# Floppy_V2_5_1_production.net
KiCad netlist of a schematic drawn in EAGLE
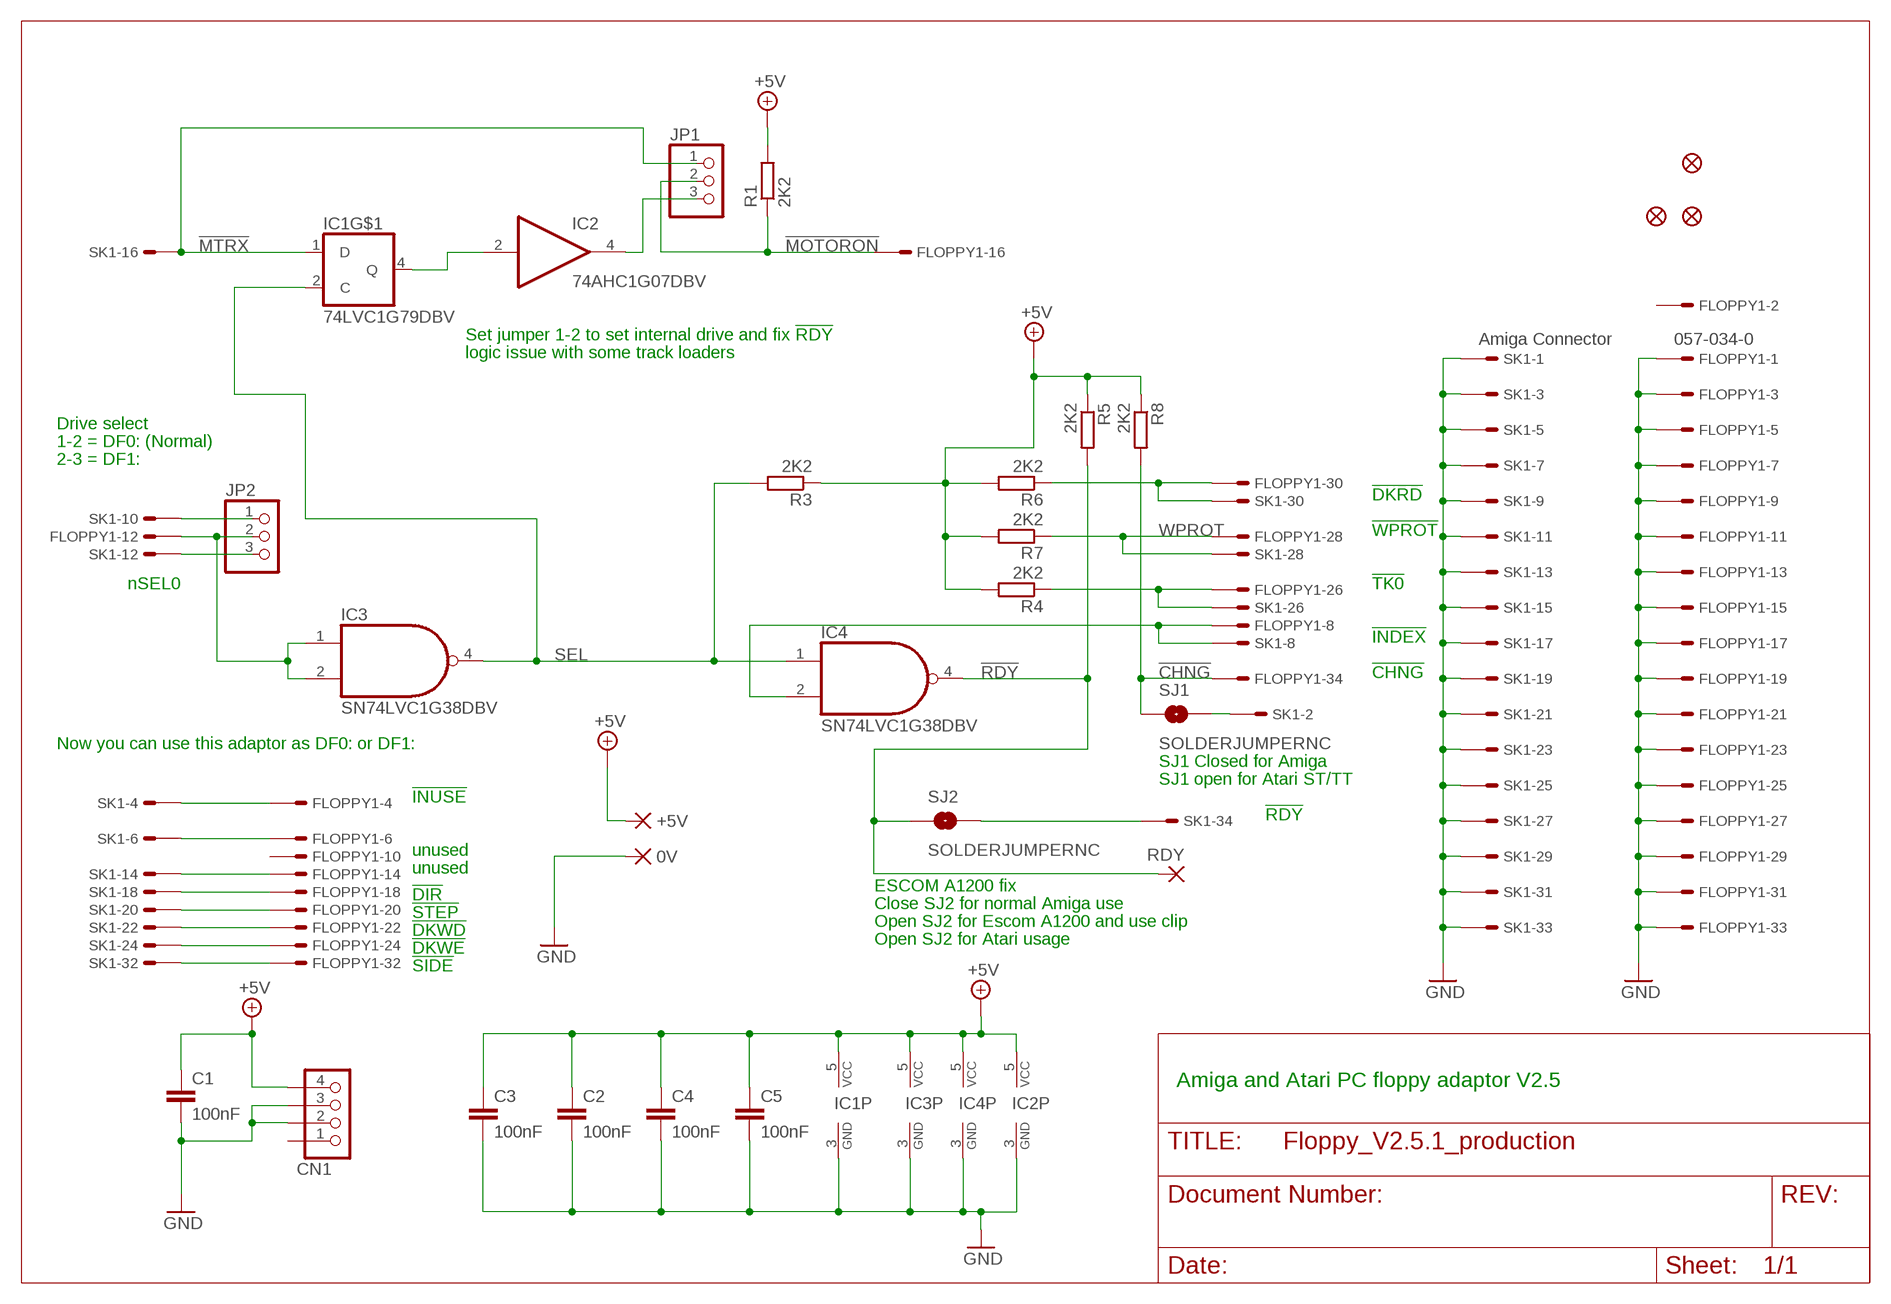
[diagram p0: schematic, sheet 1]

(export (version "E")
  (design (tool "Eeschema 10.0.6"))
  (components
    (comp (ref "+5V")
      (value "PAD-0360-S")
      (footprint "eagle-import:0360-S")
      (libsource (lib "eagle-import") (part "PAD-0360-S"))
    )
    (comp (ref "0V")
      (value "PAD-0360-S")
      (footprint "eagle-import:0360-S")
      (libsource (lib "eagle-import") (part "PAD-0360-S"))
    )
    (comp (ref "C1")
      (value "100nF")
      (footprint "eagle-import:C0603")
      (libsource (lib "eagle-import") (part "C-EUC0603"))
    )
    (comp (ref "C2")
      (value "100nF")
      (footprint "eagle-import:C0603")
      (libsource (lib "eagle-import") (part "C-EUC0603"))
    )
    (comp (ref "C3")
      (value "100nF")
      (footprint "eagle-import:C0603")
      (libsource (lib "eagle-import") (part "C-EUC0603"))
    )
    (comp (ref "C4")
      (value "100nF")
      (footprint "eagle-import:C0603")
      (libsource (lib "eagle-import") (part "C-EUC0603"))
    )
    (comp (ref "C5")
      (value "100nF")
      (footprint "eagle-import:C0603")
      (libsource (lib "eagle-import") (part "C-EUC0603"))
    )
    (comp (ref "CN1")
      (value "IANS_FLOPPY_RA")
      (footprint "eagle-import:IANS_FLOPPYPOWER__RA")
      (libsource (lib "eagle-import") (part "IANS_FLOPPY_RA"))
    )
    (comp (ref "FLOPPY1")
      (value "057-034-0")
      (footprint "eagle-import:057-034-0")
      (libsource (lib "eagle-import") (part "057-034-0"))
    )
    (comp (ref "IC1")
      (value "74LVC1G79DBV")
      (footprint "eagle-import:SOT23-5")
      (libsource (lib "eagle-import") (part "741G79DBVLVC"))
    )
    (comp (ref "IC2")
      (value "74AHC1G07DBV")
      (footprint "eagle-import:SOT23-5")
      (libsource (lib "eagle-import") (part "741G07DBVAHC"))
    )
    (comp (ref "IC3")
      (value "SN74LVC1G38DBV")
      (footprint "eagle-import:SOT23-5")
      (libsource (lib "eagle-import") (part "741G00DBVAHC"))
    )
    (comp (ref "IC4")
      (value "SN74LVC1G38DBV")
      (footprint "eagle-import:SOT23-5")
      (libsource (lib "eagle-import") (part "741G00DBVAHC"))
    )
    (comp (ref "JP1")
      (value "PINHD-1X3")
      (footprint "eagle-import:1X03")
      (libsource (lib "eagle-import") (part "PINHD-1X3"))
    )
    (comp (ref "JP2")
      (value "PINHD-1X3")
      (footprint "eagle-import:1X03")
      (libsource (lib "eagle-import") (part "PINHD-1X3"))
    )
    (comp (ref "JP3")
      (value "FIDUCIAL1X2")
      (footprint "eagle-import:FIDUCIAL-1X2")
      (libsource (lib "eagle-import") (part "FIDUCIAL1X2"))
    )
    (comp (ref "JP4")
      (value "FIDUCIAL1X2")
      (footprint "eagle-import:FIDUCIAL-1X2")
      (libsource (lib "eagle-import") (part "FIDUCIAL1X2"))
    )
    (comp (ref "JP5")
      (value "FIDUCIAL1X2")
      (footprint "eagle-import:FIDUCIAL-1X2")
      (libsource (lib "eagle-import") (part "FIDUCIAL1X2"))
    )
    (comp (ref "R1")
      (value "2K2")
      (footprint "eagle-import:R0603")
      (libsource (lib "eagle-import") (part "R-EU_R0603"))
    )
    (comp (ref "R3")
      (value "2K2")
      (footprint "eagle-import:R0603")
      (libsource (lib "eagle-import") (part "R-EU_R0603"))
    )
    (comp (ref "R4")
      (value "2K2")
      (footprint "eagle-import:R0603")
      (libsource (lib "eagle-import") (part "R-EU_R0603"))
    )
    (comp (ref "R5")
      (value "2K2")
      (footprint "eagle-import:R0603")
      (libsource (lib "eagle-import") (part "R-EU_R0603"))
    )
    (comp (ref "R6")
      (value "2K2")
      (footprint "eagle-import:R0603")
      (libsource (lib "eagle-import") (part "R-EU_R0603"))
    )
    (comp (ref "R7")
      (value "2K2")
      (footprint "eagle-import:R0603")
      (libsource (lib "eagle-import") (part "R-EU_R0603"))
    )
    (comp (ref "R8")
      (value "2K2")
      (footprint "eagle-import:R0603")
      (libsource (lib "eagle-import") (part "R-EU_R0603"))
    )
    (comp (ref "RDY")
      (value "2,15/1,0")
      (footprint "eagle-import:2,15_1,0")
      (libsource (lib "eagle-import") (part "2,15/1,0"))
    )
    (comp (ref "SJ1")
      (value "SOLDERJUMPERNC")
      (footprint "eagle-import:SJ_2S")
      (libsource (lib "eagle-import") (part "SOLDERJUMPERNC"))
    )
    (comp (ref "SJ2")
      (value "SOLDERJUMPERNC")
      (footprint "eagle-import:SJ_2S")
      (libsource (lib "eagle-import") (part "SOLDERJUMPERNC"))
    )
    (comp (ref "SK1")
      (value "Amiga Connector")
      (footprint "eagle-import:057-034-1")
      (libsource (lib "eagle-import") (part "con-panduit_057-034-1"))
    )
  )
  (nets
    (net (code "1") (name "+5V") (class "Default")
      (node (ref "+5V") (pin "P$1") (pinfunction "P_P$1") (pintype "passive"))
      (node (ref "C1") (pin "1") (pinfunction "1_1") (pintype "passive"))
      (node (ref "C2") (pin "1") (pinfunction "1_1") (pintype "passive"))
      (node (ref "C3") (pin "1") (pinfunction "1_1") (pintype "passive"))
      (node (ref "C4") (pin "1") (pinfunction "1_1") (pintype "passive"))
      (node (ref "C5") (pin "1") (pinfunction "1_1") (pintype "passive"))
      (node (ref "CN1") (pin "4") (pinfunction "+5V_4") (pintype "passive"))
      (node (ref "IC1") (pin "5") (pinfunction "VCC_5") (pintype "power_in"))
      (node (ref "IC2") (pin "5") (pinfunction "VCC_5") (pintype "power_in"))
      (node (ref "IC3") (pin "5") (pinfunction "VCC_5") (pintype "power_in"))
      (node (ref "IC4") (pin "5") (pinfunction "VCC_5") (pintype "power_in"))
      (node (ref "R1") (pin "2") (pinfunction "2_2") (pintype "passive"))
      (node (ref "R3") (pin "1") (pinfunction "1_1") (pintype "passive"))
      (node (ref "R4") (pin "2") (pinfunction "2_2") (pintype "passive"))
      (node (ref "R5") (pin "1") (pinfunction "1_1") (pintype "passive"))
      (node (ref "R6") (pin "2") (pinfunction "2_2") (pintype "passive"))
      (node (ref "R7") (pin "2") (pinfunction "2_2") (pintype "passive"))
      (node (ref "R8") (pin "1") (pinfunction "1_1") (pintype "passive"))
    )
    (net (code "2") (name "/SEL") (class "Default")
      (node (ref "IC1") (pin "2") (pinfunction "C_2") (pintype "input"))
      (node (ref "IC3") (pin "4") (pinfunction "O_4") (pintype "output"))
      (node (ref "IC4") (pin "1") (pinfunction "I0_1") (pintype "input"))
      (node (ref "R3") (pin "2") (pinfunction "2_2") (pintype "passive"))
    )
    (net (code "3") (name "/WPROT") (class "Default")
      (node (ref "FLOPPY1") (pin "28") (pinfunction "S_28") (pintype "passive"))
      (node (ref "R7") (pin "1") (pinfunction "1_1") (pintype "passive"))
      (node (ref "SK1") (pin "28") (pinfunction "S_28") (pintype "passive"))
    )
    (net (code "4") (name "/~{CHNG}") (class "Default")
      (node (ref "FLOPPY1") (pin "34") (pinfunction "S_34") (pintype "passive"))
      (node (ref "R8") (pin "2") (pinfunction "2_2") (pintype "passive"))
      (node (ref "SJ1") (pin "1") (pinfunction "1_1") (pintype "passive"))
    )
    (net (code "5") (name "/~{MOTORON}") (class "Default")
      (node (ref "FLOPPY1") (pin "16") (pinfunction "S_16") (pintype "passive"))
      (node (ref "JP1") (pin "2") (pinfunction "2_2") (pintype "passive"))
      (node (ref "R1") (pin "1") (pinfunction "1_1") (pintype "passive"))
    )
    (net (code "6") (name "/~{MTRX}") (class "Default")
      (node (ref "IC1") (pin "1") (pinfunction "D_1") (pintype "input"))
      (node (ref "JP1") (pin "1") (pinfunction "1_1") (pintype "passive"))
      (node (ref "SK1") (pin "16") (pinfunction "S_16") (pintype "passive"))
    )
    (net (code "7") (name "/~{RDY}") (class "Default")
      (node (ref "IC4") (pin "4") (pinfunction "O_4") (pintype "output"))
      (node (ref "R5") (pin "2") (pinfunction "2_2") (pintype "passive"))
      (node (ref "RDY") (pin "1") (pinfunction "P_1") (pintype "passive"))
      (node (ref "SJ2") (pin "1") (pinfunction "1_1") (pintype "passive"))
    )
    (net (code "8") (name "GND") (class "Default")
      (node (ref "0V") (pin "P$1") (pinfunction "P_P$1") (pintype "passive"))
      (node (ref "C1") (pin "2") (pinfunction "2_2") (pintype "passive"))
      (node (ref "C2") (pin "2") (pinfunction "2_2") (pintype "passive"))
      (node (ref "C3") (pin "2") (pinfunction "2_2") (pintype "passive"))
      (node (ref "C4") (pin "2") (pinfunction "2_2") (pintype "passive"))
      (node (ref "C5") (pin "2") (pinfunction "2_2") (pintype "passive"))
      (node (ref "CN1") (pin "2") (pinfunction "GND_2") (pintype "passive"))
      (node (ref "CN1") (pin "3") (pinfunction "GND_3") (pintype "passive"))
      (node (ref "FLOPPY1") (pin "1") (pinfunction "S_1") (pintype "passive"))
      (node (ref "FLOPPY1") (pin "11") (pinfunction "S_11") (pintype "passive"))
      (node (ref "FLOPPY1") (pin "13") (pinfunction "S_13") (pintype "passive"))
      (node (ref "FLOPPY1") (pin "15") (pinfunction "S_15") (pintype "passive"))
      (node (ref "FLOPPY1") (pin "17") (pinfunction "S_17") (pintype "passive"))
      (node (ref "FLOPPY1") (pin "19") (pinfunction "S_19") (pintype "passive"))
      (node (ref "FLOPPY1") (pin "21") (pinfunction "S_21") (pintype "passive"))
      (node (ref "FLOPPY1") (pin "23") (pinfunction "S_23") (pintype "passive"))
      (node (ref "FLOPPY1") (pin "25") (pinfunction "S_25") (pintype "passive"))
      (node (ref "FLOPPY1") (pin "27") (pinfunction "S_27") (pintype "passive"))
      (node (ref "FLOPPY1") (pin "29") (pinfunction "S_29") (pintype "passive"))
      (node (ref "FLOPPY1") (pin "3") (pinfunction "S_3") (pintype "passive"))
      (node (ref "FLOPPY1") (pin "31") (pinfunction "S_31") (pintype "passive"))
      (node (ref "FLOPPY1") (pin "33") (pinfunction "S_33") (pintype "passive"))
      (node (ref "FLOPPY1") (pin "5") (pinfunction "S_5") (pintype "passive"))
      (node (ref "FLOPPY1") (pin "7") (pinfunction "S_7") (pintype "passive"))
      (node (ref "FLOPPY1") (pin "9") (pinfunction "S_9") (pintype "passive"))
      (node (ref "IC1") (pin "3") (pinfunction "GND_3") (pintype "power_in"))
      (node (ref "IC2") (pin "3") (pinfunction "GND_3") (pintype "power_in"))
      (node (ref "IC3") (pin "3") (pinfunction "GND_3") (pintype "power_in"))
      (node (ref "IC4") (pin "3") (pinfunction "GND_3") (pintype "power_in"))
      (node (ref "SK1") (pin "1") (pinfunction "S_1") (pintype "passive"))
      (node (ref "SK1") (pin "11") (pinfunction "S_11") (pintype "passive"))
      (node (ref "SK1") (pin "13") (pinfunction "S_13") (pintype "passive"))
      (node (ref "SK1") (pin "15") (pinfunction "S_15") (pintype "passive"))
      (node (ref "SK1") (pin "17") (pinfunction "S_17") (pintype "passive"))
      (node (ref "SK1") (pin "19") (pinfunction "S_19") (pintype "passive"))
      (node (ref "SK1") (pin "21") (pinfunction "S_21") (pintype "passive"))
      (node (ref "SK1") (pin "23") (pinfunction "S_23") (pintype "passive"))
      (node (ref "SK1") (pin "25") (pinfunction "S_25") (pintype "passive"))
      (node (ref "SK1") (pin "27") (pinfunction "S_27") (pintype "passive"))
      (node (ref "SK1") (pin "29") (pinfunction "S_29") (pintype "passive"))
      (node (ref "SK1") (pin "3") (pinfunction "S_3") (pintype "passive"))
      (node (ref "SK1") (pin "31") (pinfunction "S_31") (pintype "passive"))
      (node (ref "SK1") (pin "33") (pinfunction "S_33") (pintype "passive"))
      (node (ref "SK1") (pin "5") (pinfunction "S_5") (pintype "passive"))
      (node (ref "SK1") (pin "7") (pinfunction "S_7") (pintype "passive"))
      (node (ref "SK1") (pin "9") (pinfunction "S_9") (pintype "passive"))
    )
    (net (code "9") (name "Net-(FLOPPY1AC-S)") (class "Default")
      (node (ref "FLOPPY1") (pin "4") (pinfunction "S_4") (pintype "passive"))
      (node (ref "SK1") (pin "4") (pinfunction "S_4") (pintype "passive"))
    )
    (net (code "10") (name "Net-(FLOPPY1AE-S)") (class "Default")
      (node (ref "FLOPPY1") (pin "6") (pinfunction "S_6") (pintype "passive"))
      (node (ref "SK1") (pin "6") (pinfunction "S_6") (pintype "passive"))
    )
    (net (code "11") (name "Net-(FLOPPY1AG-S)") (class "Default")
      (node (ref "FLOPPY1") (pin "8") (pinfunction "S_8") (pintype "passive"))
      (node (ref "IC4") (pin "2") (pinfunction "I1_2") (pintype "input"))
      (node (ref "SK1") (pin "8") (pinfunction "S_8") (pintype "passive"))
    )
    (net (code "12") (name "Net-(FLOPPY1D-S)") (class "Default")
      (node (ref "FLOPPY1") (pin "12") (pinfunction "S_12") (pintype "passive"))
      (node (ref "IC3") (pin "1") (pinfunction "I0_1") (pintype "input"))
      (node (ref "IC3") (pin "2") (pinfunction "I1_2") (pintype "input"))
      (node (ref "JP2") (pin "2") (pinfunction "2_2") (pintype "passive"))
    )
    (net (code "13") (name "Net-(FLOPPY1F-S)") (class "Default")
      (node (ref "FLOPPY1") (pin "14") (pinfunction "S_14") (pintype "passive"))
      (node (ref "SK1") (pin "14") (pinfunction "S_14") (pintype "passive"))
    )
    (net (code "14") (name "Net-(FLOPPY1J-S)") (class "Default")
      (node (ref "FLOPPY1") (pin "18") (pinfunction "S_18") (pintype "passive"))
      (node (ref "SK1") (pin "18") (pinfunction "S_18") (pintype "passive"))
    )
    (net (code "15") (name "Net-(FLOPPY1M-S)") (class "Default")
      (node (ref "FLOPPY1") (pin "20") (pinfunction "S_20") (pintype "passive"))
      (node (ref "SK1") (pin "20") (pinfunction "S_20") (pintype "passive"))
    )
    (net (code "16") (name "Net-(FLOPPY1O-S)") (class "Default")
      (node (ref "FLOPPY1") (pin "22") (pinfunction "S_22") (pintype "passive"))
      (node (ref "SK1") (pin "22") (pinfunction "S_22") (pintype "passive"))
    )
    (net (code "17") (name "Net-(FLOPPY1Q-S)") (class "Default")
      (node (ref "FLOPPY1") (pin "24") (pinfunction "S_24") (pintype "passive"))
      (node (ref "SK1") (pin "24") (pinfunction "S_24") (pintype "passive"))
    )
    (net (code "18") (name "Net-(FLOPPY1S-S)") (class "Default")
      (node (ref "FLOPPY1") (pin "26") (pinfunction "S_26") (pintype "passive"))
      (node (ref "R4") (pin "1") (pinfunction "1_1") (pintype "passive"))
      (node (ref "SK1") (pin "26") (pinfunction "S_26") (pintype "passive"))
    )
    (net (code "19") (name "Net-(FLOPPY1X-S)") (class "Default")
      (node (ref "FLOPPY1") (pin "30") (pinfunction "S_30") (pintype "passive"))
      (node (ref "R6") (pin "1") (pinfunction "1_1") (pintype "passive"))
      (node (ref "SK1") (pin "30") (pinfunction "S_30") (pintype "passive"))
    )
    (net (code "20") (name "Net-(FLOPPY1Z-S)") (class "Default")
      (node (ref "FLOPPY1") (pin "32") (pinfunction "S_32") (pintype "passive"))
      (node (ref "SK1") (pin "32") (pinfunction "S_32") (pintype "passive"))
    )
    (net (code "21") (name "Net-(IC1A-Q)") (class "Default")
      (node (ref "IC1") (pin "4") (pinfunction "Q_4") (pintype "output"))
      (node (ref "IC2") (pin "2") (pinfunction "I_2") (pintype "input"))
    )
    (net (code "22") (name "Net-(IC2A-O)") (class "Default")
      (node (ref "IC2") (pin "4") (pinfunction "O_4") (pintype "open_collector"))
      (node (ref "JP1") (pin "3") (pinfunction "3_3") (pintype "passive"))
    )
    (net (code "23") (name "Net-(SK1AB-S)") (class "Default")
      (node (ref "SJ2") (pin "2") (pinfunction "2_2") (pintype "passive"))
      (node (ref "SK1") (pin "34") (pinfunction "S_34") (pintype "passive"))
    )
    (net (code "24") (name "Net-(SK1B-S)") (class "Default")
      (node (ref "JP2") (pin "1") (pinfunction "1_1") (pintype "passive"))
      (node (ref "SK1") (pin "10") (pinfunction "S_10") (pintype "passive"))
    )
    (net (code "25") (name "Net-(SK1D-S)") (class "Default")
      (node (ref "JP2") (pin "3") (pinfunction "3_3") (pintype "passive"))
      (node (ref "SK1") (pin "12") (pinfunction "S_12") (pintype "passive"))
    )
    (net (code "26") (name "Net-(SK1L-S)") (class "Default")
      (node (ref "SJ1") (pin "2") (pinfunction "2_2") (pintype "passive"))
      (node (ref "SK1") (pin "2") (pinfunction "S_2") (pintype "passive"))
    )
    (net (code "27") (name "unconnected-(CN1-+12V-Pad1)") (class "Default")
      (node (ref "CN1") (pin "1") (pinfunction "+12V_1") (pintype "passive"))
    )
    (net (code "28") (name "unconnected-(FLOPPY1B-S-Pad10)") (class "Default")
      (node (ref "FLOPPY1") (pin "10") (pinfunction "S_10") (pintype "passive"))
    )
    (net (code "29") (name "unconnected-(FLOPPY1L-S-Pad2)") (class "Default")
      (node (ref "FLOPPY1") (pin "2") (pinfunction "S_2") (pintype "passive"))
    )
  )
)
